# OutputFilter.net
KiCad netlist of a schematic drawn in Altium Designer
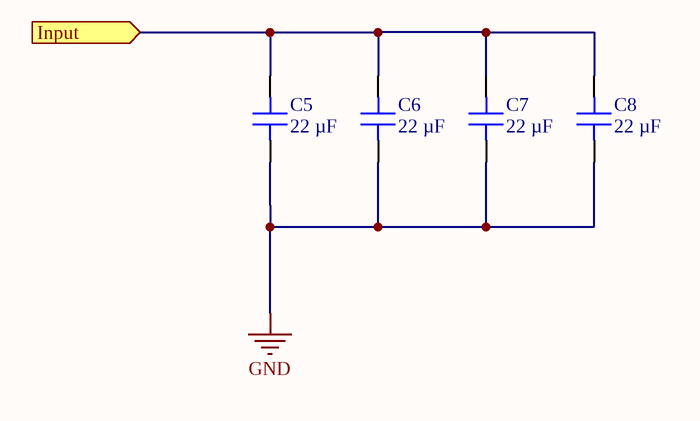
[diagram p0: OutputFilter.SchDoc]

(export (version "E")
  (design (tool "Eeschema 10.0.6"))
  (components
    (comp (ref "C5")
      (value "22 µF")
      (footprint "CAP 1812_4532 1.1MM")
      (description "CAP CER 22UF 25V X7R 1812")
      (fields
        (field (name "PART NUMBER") "CGA8P1X7R1E226M250KC")
        (field (name "MANUFACTURER") "TDK Corporation")
      )
      (libsource (lib "Celestial Altium Library - altium_library") (part "Capacitor"))
    )
    (comp (ref "C6")
      (value "22 µF")
      (footprint "CAP 1812_4532 1.1MM")
      (description "CAP CER 22UF 25V X7R 1812")
      (fields
        (field (name "PART NUMBER") "CGA8P1X7R1E226M250KC")
        (field (name "MANUFACTURER") "TDK Corporation")
      )
      (libsource (lib "Celestial Altium Library - altium_library") (part "Capacitor"))
    )
    (comp (ref "C7")
      (value "22 µF")
      (footprint "CAP 1812_4532 1.1MM")
      (description "CAP CER 22UF 25V X7R 1812")
      (fields
        (field (name "PART NUMBER") "CGA8P1X7R1E226M250KC")
        (field (name "MANUFACTURER") "TDK Corporation")
      )
      (libsource (lib "Celestial Altium Library - altium_library") (part "Capacitor"))
    )
    (comp (ref "C8")
      (value "22 µF")
      (footprint "CAP 1812_4532 1.1MM")
      (description "CAP CER 22UF 25V X7R 1812")
      (fields
        (field (name "PART NUMBER") "CGA8P1X7R1E226M250KC")
        (field (name "MANUFACTURER") "TDK Corporation")
      )
      (libsource (lib "Celestial Altium Library - altium_library") (part "Capacitor"))
    )
  )
  (nets
    (net (code "1") (name "/Input") (class "Default")
      (node (ref "C5") (pin "2") (pinfunction "2_2") (pintype "passive"))
      (node (ref "C6") (pin "2") (pinfunction "2_2") (pintype "passive"))
      (node (ref "C7") (pin "2") (pinfunction "2_2") (pintype "passive"))
      (node (ref "C8") (pin "2") (pinfunction "2_2") (pintype "passive"))
    )
    (net (code "2") (name "GND") (class "Default")
      (node (ref "C5") (pin "1") (pinfunction "1_1") (pintype "passive"))
      (node (ref "C6") (pin "1") (pinfunction "1_1") (pintype "passive"))
      (node (ref "C7") (pin "1") (pinfunction "1_1") (pintype "passive"))
      (node (ref "C8") (pin "1") (pinfunction "1_1") (pintype "passive"))
    )
  )
)
